# openSX70_U2_V6-3-1-20190307.net
KiCad netlist of a schematic drawn in EAGLE
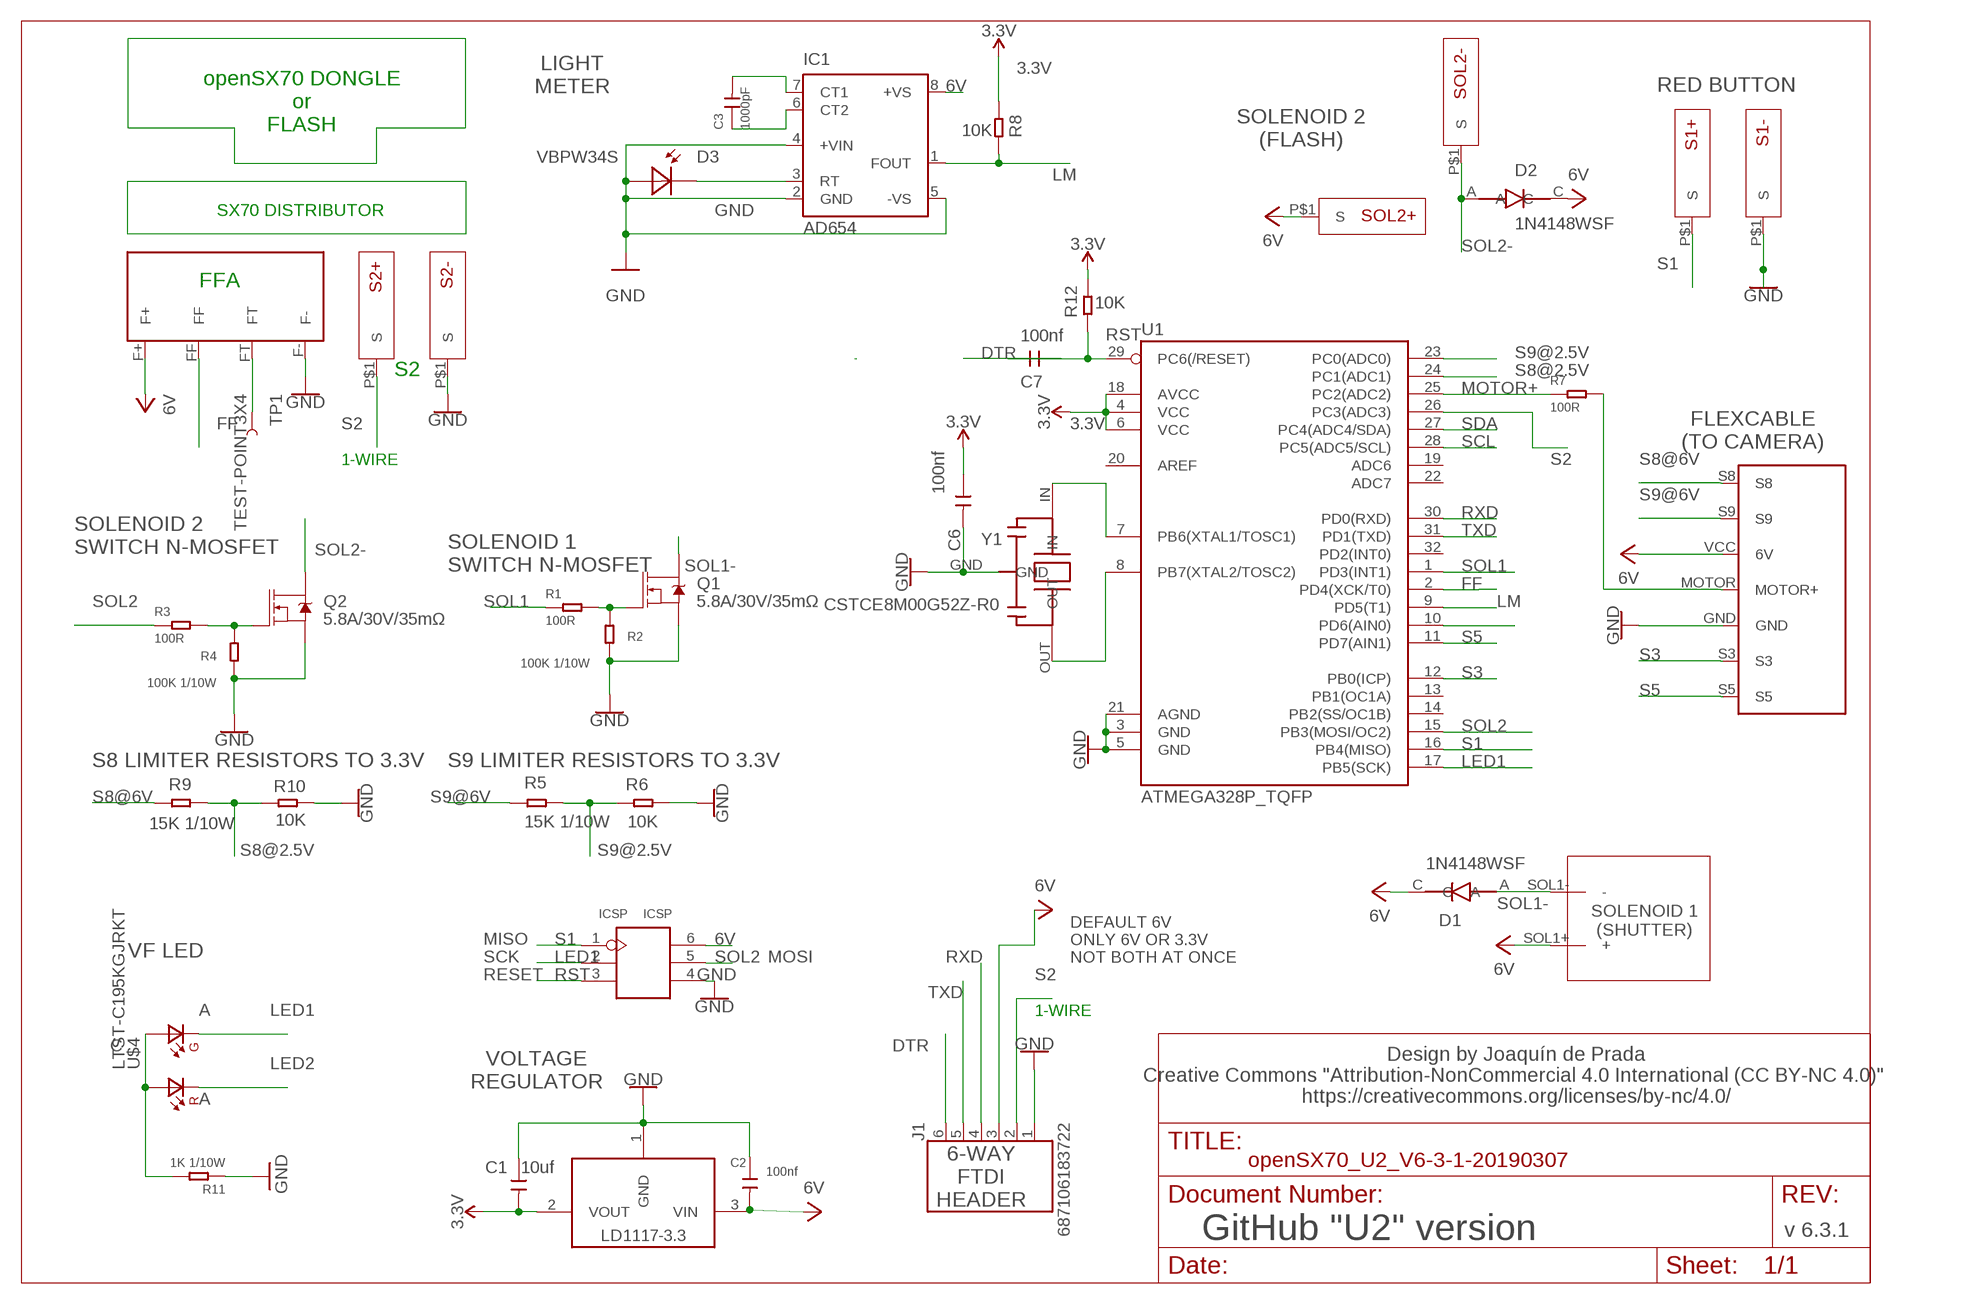
[diagram p0: schematic, sheet 1]

(export (version "E")
  (design (tool "Eeschema 10.0.6"))
  (components
    (comp (ref "C1")
      (value "10uf")
      (footprint "eagle-import:C0603")
      (fields (field (name "MPN") "CC0603KRX5R6BB106"))
      (libsource (lib "eagle-import") (part "CERAMIC-10UF-10V-10%-X5R(0603)"))
    )
    (comp (ref "C2")
      (value "100nf")
      (footprint "eagle-import:C0603")
      (fields (field (name "MPN") "CC0603KRX7R9BB104"))
      (libsource (lib "eagle-import") (part "CERAMIC-100NF-50V-10%-X7R(0603)"))
    )
    (comp (ref "C3")
      (value "1000pF")
      (footprint "eagle-import:C0603")
      (fields (field (name "MPN") "CC0603KRX7R9BB104"))
      (libsource (lib "eagle-import") (part "CERAMIC-100NF-50V-10%-X7R(0603)"))
    )
    (comp (ref "C6")
      (value "100nf")
      (footprint "eagle-import:C0603")
      (fields (field (name "MPN") "CC0603KRX7R9BB104"))
      (libsource (lib "eagle-import") (part "CERAMIC-100NF-50V-10%-X7R(0603)"))
    )
    (comp (ref "C7")
      (value "100nf")
      (footprint "eagle-import:C0603")
      (fields (field (name "MPN") "CC0603KRX7R9BB104"))
      (libsource (lib "eagle-import") (part "CERAMIC-100NF-50V-10%-X7R(0603)"))
    )
    (comp (ref "D1")
      (value "1N4148WSF")
      (footprint "eagle-import:SODFL2512X100N")
      (fields (field (name "MANUFACTURER") "Fairchild Semiconductor"))
      (libsource (lib "eagle-import") (part "1N4148WS"))
    )
    (comp (ref "D2")
      (value "1N4148WSF")
      (footprint "eagle-import:SODFL2512X100N")
      (fields (field (name "MANUFACTURER") "Fairchild Semiconductor"))
      (libsource (lib "eagle-import") (part "1N4148WS"))
    )
    (comp (ref "D3")
      (value "VBPW34S")
      (footprint "eagle-import:SOD6439X130N")
      (fields (field (name "DIGI-KEY_PART_NUMBER") "751-1500-1-ND") (field (name "MF") "Vishay"))
      (libsource (lib "eagle-import") (part "VBPW34S"))
    )
    (comp (ref "IC1")
      (value "AD654")
      (footprint "eagle-import:SOIC8")
      (libsource (lib "eagle-import") (part "AD654"))
    )
    (comp (ref "ICSP")
      (value "ICSP")
      (footprint "eagle-import:H2X3-2.54")
      (libsource (lib "eagle-import") (part "ICSP"))
    )
    (comp (ref "J1")
      (value "687106183722")
      (footprint "eagle-import:687106183722")
      (fields (field (name "MF") "Wurth Electronics"))
      (libsource (lib "eagle-import") (part "687106183722"))
    )
    (comp (ref "LD11172.5V")
      (value "LD1117 2.5V")
      (footprint "eagle-import:SOT223")
      (fields (field (name "MF") "Advanced Monolithic Systems") (field (name "MP") "AMS1117-5.0"))
      (libsource (lib "eagle-import") (part "LD1117-3.3"))
    )
    (comp (ref "Q1")
      (value "5.8A/30V/35mΩ")
      (footprint "eagle-import:SOT23-3")
      (libsource (lib "eagle-import") (part "MOSFET-NCH-AO3404A"))
    )
    (comp (ref "Q2")
      (value "5.8A/30V/35mΩ")
      (footprint "eagle-import:SOT23-3")
      (libsource (lib "eagle-import") (part "MOSFET-NCH-AO3404A"))
    )
    (comp (ref "R1")
      (value "100R")
      (footprint "eagle-import:R0603")
      (fields (field (name "MPN") "RC0603JR-07100RL"))
      (libsource (lib "eagle-import") (part "SMD-RES-100R-5%-1/10W(0603)"))
    )
    (comp (ref "R2")
      (value "100K 1/10W")
      (footprint "eagle-import:R0603")
      (fields (field (name "MPN") "RC0603JR-07100KL"))
      (libsource (lib "eagle-import") (part "SMD-RES-100K-5%-1/10W(0603)"))
    )
    (comp (ref "R3")
      (value "100R")
      (footprint "eagle-import:R0603")
      (fields (field (name "MPN") "RC0603JR-07100RL"))
      (libsource (lib "eagle-import") (part "SMD-RES-100R-5%-1/10W(0603)"))
    )
    (comp (ref "R4")
      (value "100K 1/10W")
      (footprint "eagle-import:R0603")
      (fields (field (name "MPN") "RC0603JR-07100KL"))
      (libsource (lib "eagle-import") (part "SMD-RES-100K-5%-1/10W(0603)"))
    )
    (comp (ref "R5")
      (value "15K 1/10W")
      (footprint "eagle-import:R0603")
      (fields (field (name "MPN") "RC0603FR-0715KL"))
      (libsource (lib "eagle-import") (part "SMD-RES-15K-1%-1/10W(0603)"))
    )
    (comp (ref "R6")
      (value "10K")
      (footprint "eagle-import:R0603")
      (fields (field (name "MPN") "RC0603FR-0710KL"))
      (libsource (lib "eagle-import") (part "SMD-RES-10K-1%-1/10W(0603)"))
    )
    (comp (ref "R7")
      (value "100R")
      (footprint "eagle-import:R0603")
      (fields (field (name "MPN") "RC0603JR-07100RL"))
      (libsource (lib "eagle-import") (part "SMD-RES-100R-5%-1/10W(0603)"))
    )
    (comp (ref "R8")
      (value "10K")
      (footprint "eagle-import:R0603")
      (fields (field (name "MPN") "RC0603FR-0710KL"))
      (libsource (lib "eagle-import") (part "SMD-RES-10K-1%-1/10W(0603)"))
    )
    (comp (ref "R9")
      (value "15K 1/10W")
      (footprint "eagle-import:R0603")
      (fields (field (name "MPN") "RC0603FR-0715KL"))
      (libsource (lib "eagle-import") (part "SMD-RES-15K-1%-1/10W(0603)"))
    )
    (comp (ref "R10")
      (value "10K")
      (footprint "eagle-import:R0603")
      (fields (field (name "MPN") "RC0603FR-0710KL"))
      (libsource (lib "eagle-import") (part "SMD-RES-10K-1%-1/10W(0603)"))
    )
    (comp (ref "R11")
      (value "1K 1/10W")
      (footprint "eagle-import:R0603")
      (fields (field (name "MPN") "RC0603JR-071KL"))
      (libsource (lib "eagle-import") (part "SMD-RES-1K-5%-1/10W(0603)"))
    )
    (comp (ref "R12")
      (value "10K")
      (footprint "eagle-import:R0603")
      (fields (field (name "MPN") "RC0603FR-0710KL"))
      (libsource (lib "eagle-import") (part "SMD-RES-10K-1%-1/10W(0603)"))
    )
    (comp (ref "S1+")
      (value "SX70-S-PAD-NEW")
      (footprint "eagle-import:SX70-S-PAD2")
      (libsource (lib "eagle-import") (part "SX70-S-PAD-NEW"))
    )
    (comp (ref "S1-")
      (value "SX70-S-PAD-NEW")
      (footprint "eagle-import:SX70-S-PAD2")
      (libsource (lib "eagle-import") (part "SX70-S-PAD-NEW"))
    )
    (comp (ref "S2+")
      (value "SX70-S-PAD-NEW")
      (footprint "eagle-import:SX70-S-PAD2")
      (libsource (lib "eagle-import") (part "SX70-S-PAD-NEW"))
    )
    (comp (ref "S2-")
      (value "SX70-S-PAD-NEW")
      (footprint "eagle-import:SX70-S-PAD2")
      (libsource (lib "eagle-import") (part "SX70-S-PAD-NEW"))
    )
    (comp (ref "SOL1")
      (value "SX70-SOLENOID1-2PADS")
      (footprint "eagle-import:SX70-SOLENOID1-2")
      (libsource (lib "eagle-import") (part "SX70-SOLENOID1-2PADS"))
    )
    (comp (ref "SOL2+")
      (value "SX70-S-PAD-NEW")
      (footprint "eagle-import:SX70-S-PAD2")
      (libsource (lib "eagle-import") (part "SX70-S-PAD-NEW"))
    )
    (comp (ref "SOL2-")
      (value "SX70-S-PAD-NEW")
      (footprint "eagle-import:SX70-S-PAD2")
      (libsource (lib "eagle-import") (part "SX70-S-PAD-NEW"))
    )
    (comp (ref "TP1")
      (value "TEST-POINT3X4")
      (footprint "eagle-import:PAD.03X.04")
      (libsource (lib "eagle-import") (part "TEST-POINT3X4"))
    )
    (comp (ref "U$1")
      (value "SX70-7-PAD")
      (footprint "eagle-import:SX70-7-PAD-PROPER")
      (libsource (lib "eagle-import") (part "SX70-7-PAD"))
    )
    (comp (ref "U$2")
      (value "FFA")
      (footprint "eagle-import:FFA-PAD-PACKAGE")
      (libsource (lib "eagle-import") (part "SX70-FFA-PAD"))
    )
    (comp (ref "U$4")
      (value "LTST-C195KGJRKT")
      (footprint "eagle-import:LTST-BILED-15X16")
      (fields (field (name "MF") "Lite-On Inc."))
      (libsource (lib "eagle-import") (part "LTST-C195KGJRKT"))
    )
    (comp (ref "U1")
      (value "ATMEGA328P_TQFP")
      (footprint "eagle-import:TQFP32-08")
      (libsource (lib "eagle-import") (part "ATMEGA328P_TQFP"))
    )
    (comp (ref "Y1")
      (value "CSTCE8M00G52Z-R0")
      (footprint "eagle-import:CFP95P160X100-3N")
      (fields (field (name "MF") "Murata") (field (name "MP") "CSTCE16M0V53-R0"))
      (libsource (lib "eagle-import") (part "CSTCE16M0V53-R0"))
    )
  )
  (nets
    (net (code "1") (name "/DTR") (class "Default")
      (node (ref "C7") (pin "1") (pinfunction "1_1") (pintype "passive"))
      (node (ref "J1") (pin "6") (pinfunction "1_6") (pintype "passive"))
    )
    (net (code "2") (name "/FF") (class "Default")
      (node (ref "U$2") (pin "FF") (pinfunction "FF_FF") (pintype "bidirectional"))
      (node (ref "U1") (pin "2") (pinfunction "PD4(XCK/T0)_2") (pintype "bidirectional"))
    )
    (net (code "3") (name "/LED1") (class "Default")
      (node (ref "ICSP") (pin "2") (pinfunction "SCK_2") (pintype "bidirectional"))
      (node (ref "U$4") (pin "P$3") (pinfunction "K1_P$3") (pintype "passive"))
      (node (ref "U1") (pin "17") (pinfunction "PB5(SCK)_17") (pintype "bidirectional"))
    )
    (net (code "4") (name "/LED2") (class "Default")
      (node (ref "U$4") (pin "P$4") (pinfunction "K2_P$4") (pintype "passive"))
    )
    (net (code "5") (name "/LM") (class "Default")
      (node (ref "IC1") (pin "1") (pinfunction "FOUT_1") (pintype "open_collector"))
      (node (ref "R8") (pin "2") (pinfunction "2_2") (pintype "passive"))
      (node (ref "U1") (pin "9") (pinfunction "PD5(T1)_9") (pintype "bidirectional"))
    )
    (net (code "6") (name "/MOTOR+") (class "Default")
      (node (ref "R7") (pin "1") (pinfunction "1_1") (pintype "passive"))
      (node (ref "U1") (pin "25") (pinfunction "PC2(ADC2)_25") (pintype "bidirectional"))
    )
    (net (code "7") (name "/RST") (class "Default")
      (node (ref "C7") (pin "2") (pinfunction "2_2") (pintype "passive"))
      (node (ref "ICSP") (pin "3") (pinfunction "RST_3") (pintype "bidirectional"))
      (node (ref "R12") (pin "1") (pinfunction "1_1") (pintype "passive"))
      (node (ref "U1") (pin "29") (pinfunction "PC6(/RESET)_29") (pintype "bidirectional"))
    )
    (net (code "8") (name "/RXD") (class "Default")
      (node (ref "J1") (pin "4") (pinfunction "3_4") (pintype "passive"))
      (node (ref "U1") (pin "30") (pinfunction "PD0(RXD)_30") (pintype "bidirectional"))
    )
    (net (code "9") (name "/S1") (class "Default")
      (node (ref "ICSP") (pin "1") (pinfunction "MISO_1") (pintype "bidirectional"))
      (node (ref "S1+") (pin "P$1") (pinfunction "S_P$1") (pintype "bidirectional"))
      (node (ref "U1") (pin "16") (pinfunction "PB4(MISO)_16") (pintype "bidirectional"))
    )
    (net (code "10") (name "/S2") (class "Default")
      (node (ref "J1") (pin "2") (pinfunction "5_2") (pintype "passive"))
      (node (ref "S2+") (pin "P$1") (pinfunction "S_P$1") (pintype "bidirectional"))
      (node (ref "U1") (pin "26") (pinfunction "PC3(ADC3)_26") (pintype "bidirectional"))
    )
    (net (code "11") (name "/S3") (class "Default")
      (node (ref "U$1") (pin "S3") (pinfunction "S3_S3") (pintype "bidirectional"))
      (node (ref "U1") (pin "12") (pinfunction "PB0(ICP)_12") (pintype "bidirectional"))
    )
    (net (code "12") (name "/S5") (class "Default")
      (node (ref "U$1") (pin "S5") (pinfunction "S5_S5") (pintype "bidirectional"))
      (node (ref "U1") (pin "11") (pinfunction "PD7(AIN1)_11") (pintype "bidirectional"))
    )
    (net (code "13") (name "/S8@2.5V") (class "Default")
      (node (ref "R10") (pin "1") (pinfunction "1_1") (pintype "passive"))
      (node (ref "R9") (pin "2") (pinfunction "2_2") (pintype "passive"))
      (node (ref "U1") (pin "24") (pinfunction "PC1(ADC1)_24") (pintype "bidirectional"))
    )
    (net (code "14") (name "/S8@6V") (class "Default")
      (node (ref "R9") (pin "1") (pinfunction "1_1") (pintype "passive"))
      (node (ref "U$1") (pin "S8") (pinfunction "S8_S8") (pintype "bidirectional"))
    )
    (net (code "15") (name "/S9@2.5V") (class "Default")
      (node (ref "R5") (pin "2") (pinfunction "2_2") (pintype "passive"))
      (node (ref "R6") (pin "1") (pinfunction "1_1") (pintype "passive"))
      (node (ref "U1") (pin "23") (pinfunction "PC0(ADC0)_23") (pintype "bidirectional"))
    )
    (net (code "16") (name "/S9@6V") (class "Default")
      (node (ref "R5") (pin "1") (pinfunction "1_1") (pintype "passive"))
      (node (ref "U$1") (pin "S9") (pinfunction "S9_S9") (pintype "bidirectional"))
    )
    (net (code "17") (name "/SCL") (class "Default")
      (node (ref "U1") (pin "28") (pinfunction "PC5(ADC5/SCL)_28") (pintype "bidirectional"))
    )
    (net (code "18") (name "/SDA") (class "Default")
      (node (ref "U1") (pin "27") (pinfunction "PC4(ADC4/SDA)_27") (pintype "bidirectional"))
    )
    (net (code "19") (name "/SOL1") (class "Default")
      (node (ref "R1") (pin "1") (pinfunction "1_1") (pintype "passive"))
      (node (ref "U1") (pin "1") (pinfunction "PD3(INT1)_1") (pintype "bidirectional"))
    )
    (net (code "20") (name "/SOL1-") (class "Default")
      (node (ref "D1") (pin "A") (pinfunction "A_A") (pintype "passive"))
      (node (ref "Q1") (pin "3") (pinfunction "D_3") (pintype "bidirectional"))
      (node (ref "SOL1") (pin "SOL1-") (pinfunction "-_SOL1-") (pintype "bidirectional"))
    )
    (net (code "21") (name "/SOL2") (class "Default")
      (node (ref "ICSP") (pin "5") (pinfunction "MOSI_5") (pintype "bidirectional"))
      (node (ref "R3") (pin "1") (pinfunction "1_1") (pintype "passive"))
      (node (ref "U1") (pin "15") (pinfunction "PB3(MOSI/OC2)_15") (pintype "bidirectional"))
    )
    (net (code "22") (name "/SOL2-") (class "Default")
      (node (ref "D2") (pin "A") (pinfunction "A_A") (pintype "passive"))
      (node (ref "Q2") (pin "3") (pinfunction "D_3") (pintype "bidirectional"))
      (node (ref "SOL2-") (pin "P$1") (pinfunction "S_P$1") (pintype "bidirectional"))
    )
    (net (code "23") (name "/TXD") (class "Default")
      (node (ref "J1") (pin "5") (pinfunction "2_5") (pintype "passive"))
      (node (ref "U1") (pin "31") (pinfunction "PD1(TXD)_31") (pintype "bidirectional"))
    )
    (net (code "24") (name "3.3V") (class "Default")
      (node (ref "C1") (pin "2") (pinfunction "2_2") (pintype "passive"))
      (node (ref "C6") (pin "1") (pinfunction "1_1") (pintype "passive"))
      (node (ref "LD11172.5V") (pin "2") (pinfunction "VOUT_2") (pintype "bidirectional"))
      (node (ref "R12") (pin "2") (pinfunction "2_2") (pintype "passive"))
      (node (ref "R8") (pin "1") (pinfunction "1_1") (pintype "passive"))
      (node (ref "U1") (pin "18") (pinfunction "AVCC_18") (pintype "bidirectional"))
      (node (ref "U1") (pin "4") (pinfunction "VCC_4") (pintype "bidirectional"))
      (node (ref "U1") (pin "6") (pinfunction "VCC_6") (pintype "bidirectional"))
    )
    (net (code "25") (name "6V") (class "Default")
      (node (ref "C2") (pin "2") (pinfunction "2_2") (pintype "passive"))
      (node (ref "D1") (pin "C") (pinfunction "C_C") (pintype "passive"))
      (node (ref "D2") (pin "C") (pinfunction "C_C") (pintype "passive"))
      (node (ref "IC1") (pin "8") (pinfunction "+VS_8") (pintype "power_in"))
      (node (ref "ICSP") (pin "6") (pinfunction "VCC_6") (pintype "bidirectional"))
      (node (ref "J1") (pin "3") (pinfunction "4_3") (pintype "passive"))
      (node (ref "LD11172.5V") (pin "3") (pinfunction "VIN_3") (pintype "bidirectional"))
      (node (ref "SOL1") (pin "SOL1+") (pinfunction "+_SOL1+") (pintype "bidirectional"))
      (node (ref "SOL2+") (pin "P$1") (pinfunction "S_P$1") (pintype "bidirectional"))
      (node (ref "U$1") (pin "VCC") (pinfunction "6V_VCC") (pintype "bidirectional"))
      (node (ref "U$2") (pin "F+") (pinfunction "F+_F+") (pintype "bidirectional"))
    )
    (net (code "26") (name "GND") (class "Default")
      (node (ref "C1") (pin "1") (pinfunction "1_1") (pintype "passive"))
      (node (ref "C2") (pin "1") (pinfunction "1_1") (pintype "passive"))
      (node (ref "C6") (pin "2") (pinfunction "2_2") (pintype "passive"))
      (node (ref "D3") (pin "A") (pinfunction "A_A") (pintype "passive"))
      (node (ref "IC1") (pin "2") (pinfunction "GND_2") (pintype "power_in"))
      (node (ref "IC1") (pin "4") (pinfunction "+VIN_4") (pintype "input"))
      (node (ref "IC1") (pin "5") (pinfunction "-VS_5") (pintype "power_in"))
      (node (ref "ICSP") (pin "4") (pinfunction "GND_4") (pintype "bidirectional"))
      (node (ref "J1") (pin "1") (pinfunction "6_1") (pintype "passive"))
      (node (ref "LD11172.5V") (pin "1") (pinfunction "GND_1") (pintype "bidirectional"))
      (node (ref "Q1") (pin "2") (pinfunction "S_2") (pintype "bidirectional"))
      (node (ref "Q2") (pin "2") (pinfunction "S_2") (pintype "bidirectional"))
      (node (ref "R10") (pin "2") (pinfunction "2_2") (pintype "passive"))
      (node (ref "R11") (pin "1") (pinfunction "1_1") (pintype "passive"))
      (node (ref "R2") (pin "1") (pinfunction "1_1") (pintype "passive"))
      (node (ref "R4") (pin "1") (pinfunction "1_1") (pintype "passive"))
      (node (ref "R6") (pin "2") (pinfunction "2_2") (pintype "passive"))
      (node (ref "S1-") (pin "P$1") (pinfunction "S_P$1") (pintype "bidirectional"))
      (node (ref "S2-") (pin "P$1") (pinfunction "S_P$1") (pintype "bidirectional"))
      (node (ref "U$1") (pin "GND") (pinfunction "GND_GND") (pintype "bidirectional"))
      (node (ref "U$2") (pin "F-") (pinfunction "F-_F-") (pintype "bidirectional"))
      (node (ref "U1") (pin "21") (pinfunction "AGND_21") (pintype "bidirectional"))
      (node (ref "U1") (pin "3") (pinfunction "GND_3") (pintype "bidirectional"))
      (node (ref "U1") (pin "5") (pinfunction "GND_5") (pintype "bidirectional"))
      (node (ref "Y1") (pin "GND") (pinfunction "GND_GND") (pintype "passive"))
    )
    (net (code "27") (name "Net-(IC1-CT1)") (class "Default")
      (node (ref "C3") (pin "2") (pinfunction "2_2") (pintype "passive"))
      (node (ref "IC1") (pin "7") (pinfunction "CT1_7") (pintype "passive"))
    )
    (net (code "28") (name "Net-(IC1-CT2)") (class "Default")
      (node (ref "C3") (pin "1") (pinfunction "1_1") (pintype "passive"))
      (node (ref "IC1") (pin "6") (pinfunction "CT2_6") (pintype "passive"))
    )
    (net (code "29") (name "Net-(IC1-RT)") (class "Default")
      (node (ref "D3") (pin "C") (pinfunction "C_C") (pintype "passive"))
      (node (ref "IC1") (pin "3") (pinfunction "RT_3") (pintype "passive"))
    )
    (net (code "30") (name "Net-(Q1-G)") (class "Default")
      (node (ref "Q1") (pin "1") (pinfunction "G_1") (pintype "bidirectional"))
      (node (ref "R1") (pin "2") (pinfunction "2_2") (pintype "passive"))
      (node (ref "R2") (pin "2") (pinfunction "2_2") (pintype "passive"))
    )
    (net (code "31") (name "Net-(Q2-G)") (class "Default")
      (node (ref "Q2") (pin "1") (pinfunction "G_1") (pintype "bidirectional"))
      (node (ref "R3") (pin "2") (pinfunction "2_2") (pintype "passive"))
      (node (ref "R4") (pin "2") (pinfunction "2_2") (pintype "passive"))
    )
    (net (code "32") (name "Net-(TP1-1)") (class "Default")
      (node (ref "TP1") (pin "P$1") (pinfunction "1_P$1") (pintype "bidirectional"))
      (node (ref "U$2") (pin "FT") (pinfunction "FT_FT") (pintype "bidirectional"))
    )
    (net (code "33") (name "Net-(U$1-MOTOR+)") (class "Default")
      (node (ref "R7") (pin "2") (pinfunction "2_2") (pintype "passive"))
      (node (ref "U$1") (pin "MOTOR") (pinfunction "MOTOR+_MOTOR") (pintype "bidirectional"))
    )
    (net (code "34") (name "Net-(U$4-A1)") (class "Default")
      (node (ref "R11") (pin "2") (pinfunction "2_2") (pintype "passive"))
      (node (ref "U$4") (pin "P$1") (pinfunction "A1_P$1") (pintype "passive"))
      (node (ref "U$4") (pin "P$2") (pinfunction "A2_P$2") (pintype "passive"))
    )
    (net (code "35") (name "Net-(U1-PB6(XTAL1{slash}TOSC1))") (class "Default")
      (node (ref "U1") (pin "7") (pinfunction "PB6(XTAL1/TOSC1)_7") (pintype "bidirectional"))
      (node (ref "Y1") (pin "IN") (pinfunction "IN_IN") (pintype "input"))
    )
    (net (code "36") (name "Net-(U1-PB7(XTAL2{slash}TOSC2))") (class "Default")
      (node (ref "U1") (pin "8") (pinfunction "PB7(XTAL2/TOSC2)_8") (pintype "bidirectional"))
      (node (ref "Y1") (pin "OUT") (pinfunction "OUT_OUT") (pintype "output"))
    )
    (net (code "37") (name "unconnected-(U1-ADC6-Pad19)") (class "Default")
      (node (ref "U1") (pin "19") (pinfunction "ADC6_19") (pintype "bidirectional"))
    )
    (net (code "38") (name "unconnected-(U1-ADC7-Pad22)") (class "Default")
      (node (ref "U1") (pin "22") (pinfunction "ADC7_22") (pintype "bidirectional"))
    )
    (net (code "39") (name "unconnected-(U1-AREF-Pad20)") (class "Default")
      (node (ref "U1") (pin "20") (pinfunction "AREF_20") (pintype "bidirectional"))
    )
    (net (code "40") (name "unconnected-(U1-PB1(OC1A)-Pad13)") (class "Default")
      (node (ref "U1") (pin "13") (pinfunction "PB1(OC1A)_13") (pintype "bidirectional"))
    )
    (net (code "41") (name "unconnected-(U1-PB2(SS{slash}OC1B)-Pad14)") (class "Default")
      (node (ref "U1") (pin "14") (pinfunction "PB2(SS/OC1B)_14") (pintype "bidirectional"))
    )
    (net (code "42") (name "unconnected-(U1-PD2(INT0)-Pad32)") (class "Default")
      (node (ref "U1") (pin "32") (pinfunction "PD2(INT0)_32") (pintype "bidirectional"))
    )
    (net (code "43") (name "unconnected-(U1-PD6(AIN0)-Pad10)") (class "Default")
      (node (ref "U1") (pin "10") (pinfunction "PD6(AIN0)_10") (pintype "bidirectional"))
    )
  )
)
